# brewBuddy.net
KiCad netlist of a schematic drawn in EAGLE
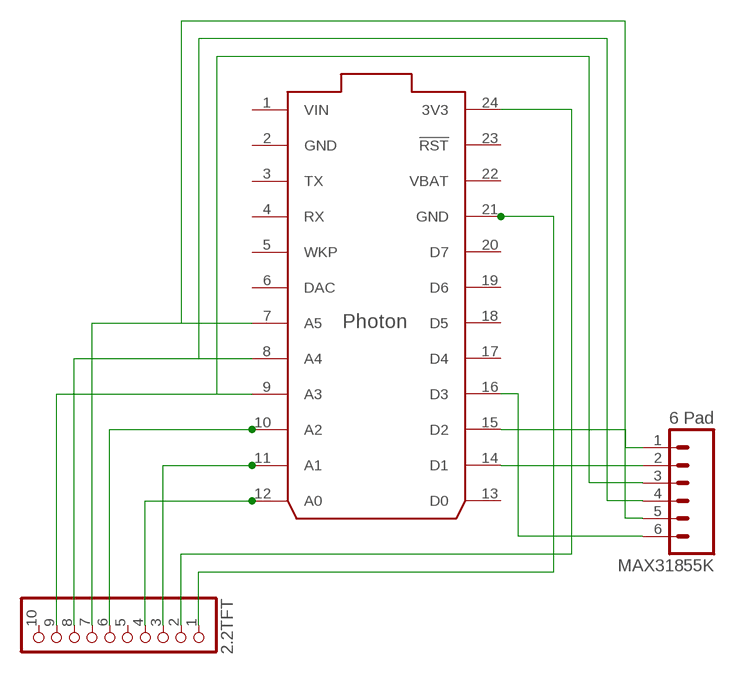
[diagram p0: schematic, sheet 1]

(export (version "E")
  (design (tool "Eeschema 10.0.6"))
  (components
    (comp (ref "2.2TFT")
      (value "MICROBUILDER_HEADER-1X101X10_2MM")
      (footprint "eagle-import:MICROBUILDER_1X10_ROUND_2MM")
      (libsource (lib "eagle-import") (part "MICROBUILDER_HEADER-1X101X10_2MM"))
    )
    (comp (ref "MAX31855K")
      (value "6 Pad")
      (footprint "eagle-import:1X06_LONGPADS")
      (libsource (lib "eagle-import") (part "M06LONGPADS"))
    )
    (comp (ref "U$1")
      (value "PHOTON_WITH_HEADERS")
      (footprint "eagle-import:PHOTON")
      (libsource (lib "eagle-import") (part "PHOTON_WITH_HEADERS"))
    )
  )
  (nets
    (net (code "1") (name "/GND") (class "Default")
      (node (ref "U$1") (pin "2") (pinfunction "GND_2") (pintype "power_in"))
    )
    (net (code "2") (name "/VBAT") (class "Default")
      (node (ref "U$1") (pin "22") (pinfunction "VBAT_22") (pintype "power_in"))
    )
    (net (code "3") (name "/VIN") (class "Default")
      (node (ref "U$1") (pin "1") (pinfunction "VIN_1") (pintype "power_in"))
    )
    (net (code "4") (name "Net-(2.2TFT-Pad1)") (class "Default")
      (node (ref "2.2TFT") (pin "1") (pinfunction "1_1") (pintype "passive"))
      (node (ref "U$1") (pin "21") (pinfunction "GND_21") (pintype "power_in"))
    )
    (net (code "5") (name "Net-(U$1-3V3)") (class "Default")
      (node (ref "2.2TFT") (pin "2") (pinfunction "2_2") (pintype "passive"))
      (node (ref "U$1") (pin "24") (pinfunction "3V3_24") (pintype "power_in"))
    )
    (net (code "6") (name "Net-(U$1-A0)") (class "Default")
      (node (ref "2.2TFT") (pin "4") (pinfunction "4_4") (pintype "passive"))
      (node (ref "U$1") (pin "12") (pinfunction "A0_12") (pintype "bidirectional"))
    )
    (net (code "7") (name "Net-(U$1-A1)") (class "Default")
      (node (ref "2.2TFT") (pin "3") (pinfunction "3_3") (pintype "passive"))
      (node (ref "U$1") (pin "11") (pinfunction "A1_11") (pintype "bidirectional"))
    )
    (net (code "8") (name "Net-(U$1-A2)") (class "Default")
      (node (ref "2.2TFT") (pin "6") (pinfunction "6_6") (pintype "passive"))
      (node (ref "U$1") (pin "10") (pinfunction "A2_10") (pintype "bidirectional"))
    )
    (net (code "9") (name "Net-(U$1-A3)") (class "Default")
      (node (ref "2.2TFT") (pin "9") (pinfunction "9_9") (pintype "passive"))
      (node (ref "MAX31855K") (pin "3") (pinfunction "3_3") (pintype "passive"))
      (node (ref "U$1") (pin "9") (pinfunction "A3_9") (pintype "bidirectional"))
    )
    (net (code "10") (name "Net-(U$1-A4)") (class "Default")
      (node (ref "2.2TFT") (pin "8") (pinfunction "8_8") (pintype "passive"))
      (node (ref "MAX31855K") (pin "4") (pinfunction "4_4") (pintype "passive"))
      (node (ref "U$1") (pin "8") (pinfunction "A4_8") (pintype "bidirectional"))
    )
    (net (code "11") (name "Net-(U$1-A5)") (class "Default")
      (node (ref "2.2TFT") (pin "7") (pinfunction "7_7") (pintype "passive"))
      (node (ref "MAX31855K") (pin "5") (pinfunction "5_5") (pintype "passive"))
      (node (ref "U$1") (pin "7") (pinfunction "A5_7") (pintype "bidirectional"))
    )
    (net (code "12") (name "Net-(U$1-D1)") (class "Default")
      (node (ref "MAX31855K") (pin "2") (pinfunction "2_2") (pintype "passive"))
      (node (ref "U$1") (pin "14") (pinfunction "D1_14") (pintype "bidirectional"))
    )
    (net (code "13") (name "Net-(U$1-D2)") (class "Default")
      (node (ref "MAX31855K") (pin "1") (pinfunction "1_1") (pintype "passive"))
      (node (ref "U$1") (pin "15") (pinfunction "D2_15") (pintype "bidirectional"))
    )
    (net (code "14") (name "Net-(U$1-D3)") (class "Default")
      (node (ref "MAX31855K") (pin "6") (pinfunction "6_6") (pintype "passive"))
      (node (ref "U$1") (pin "16") (pinfunction "D3_16") (pintype "bidirectional"))
    )
    (net (code "15") (name "unconnected-(2.2TFT-Pad5)") (class "Default")
      (node (ref "2.2TFT") (pin "5") (pinfunction "5_5") (pintype "passive"))
    )
    (net (code "16") (name "unconnected-(2.2TFT-Pad10)") (class "Default")
      (node (ref "2.2TFT") (pin "10") (pinfunction "10_10") (pintype "passive"))
    )
    (net (code "17") (name "unconnected-(U$1-D0-Pad13)") (class "Default")
      (node (ref "U$1") (pin "13") (pinfunction "D0_13") (pintype "bidirectional"))
    )
    (net (code "18") (name "unconnected-(U$1-D4-Pad17)") (class "Default")
      (node (ref "U$1") (pin "17") (pinfunction "D4_17") (pintype "bidirectional"))
    )
    (net (code "19") (name "unconnected-(U$1-D5-Pad18)") (class "Default")
      (node (ref "U$1") (pin "18") (pinfunction "D5_18") (pintype "bidirectional"))
    )
    (net (code "20") (name "unconnected-(U$1-D6-Pad19)") (class "Default")
      (node (ref "U$1") (pin "19") (pinfunction "D6_19") (pintype "bidirectional"))
    )
    (net (code "21") (name "unconnected-(U$1-D7-Pad20)") (class "Default")
      (node (ref "U$1") (pin "20") (pinfunction "D7_20") (pintype "bidirectional"))
    )
    (net (code "22") (name "unconnected-(U$1-DAC-Pad6)") (class "Default")
      (node (ref "U$1") (pin "6") (pinfunction "DAC_6") (pintype "bidirectional"))
    )
    (net (code "23") (name "unconnected-(U$1-RX-Pad4)") (class "Default")
      (node (ref "U$1") (pin "4") (pinfunction "RX_4") (pintype "bidirectional"))
    )
    (net (code "24") (name "unconnected-(U$1-TX-Pad3)") (class "Default")
      (node (ref "U$1") (pin "3") (pinfunction "TX_3") (pintype "bidirectional"))
    )
    (net (code "25") (name "unconnected-(U$1-WKP-Pad5)") (class "Default")
      (node (ref "U$1") (pin "5") (pinfunction "WKP_5") (pintype "bidirectional"))
    )
    (net (code "26") (name "unconnected-(U$1-~{RST}-Pad23)") (class "Default")
      (node (ref "U$1") (pin "23") (pinfunction "~{RST}_23") (pintype "bidirectional"))
    )
  )
)
